# REV14.net
KiCad netlist of a schematic drawn in EAGLE
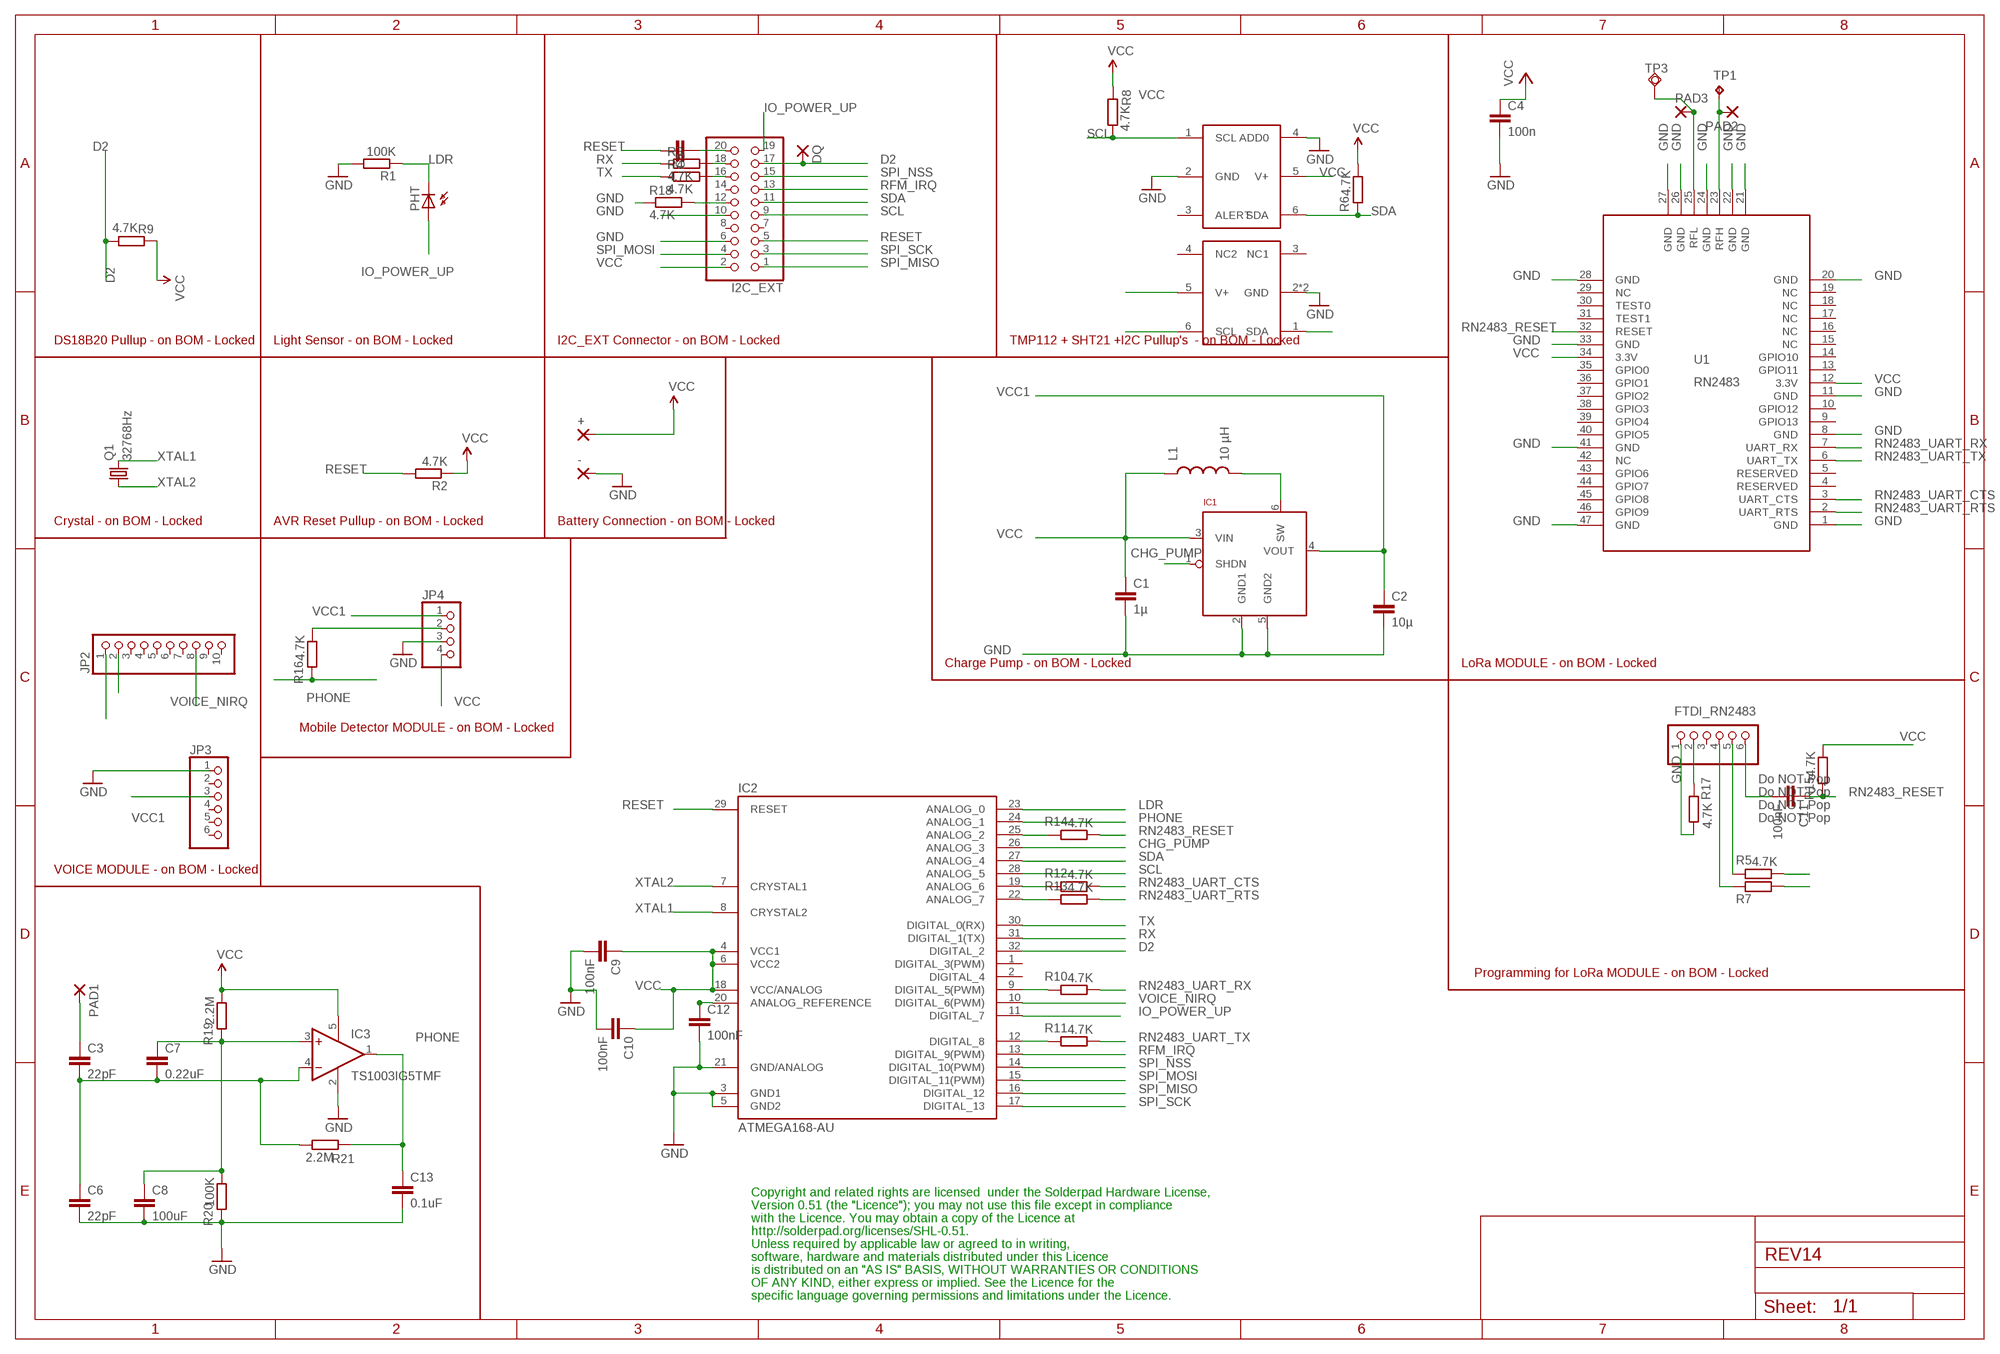
[diagram p0: schematic, sheet 1]

(export (version "E")
  (design (tool "Eeschema 10.0.6"))
  (components
    (comp (ref "+")
      (value "2,15/1,0")
      (footprint "eagle-import:2,15_1,0")
      (libsource (lib "eagle-import") (part "2,15/1,0"))
    )
    (comp (ref "-")
      (value "2,15/1,0")
      (footprint "eagle-import:2,15_1,0")
      (libsource (lib "eagle-import") (part "2,15/1,0"))
    )
    (comp (ref "C1")
      (value "1µ")
      (footprint "eagle-import:0603-CAP")
      (libsource (lib "eagle-import") (part "CAP0603-CAP"))
    )
    (comp (ref "C2")
      (value "10µ")
      (footprint "eagle-import:C0603")
      (libsource (lib "eagle-import") (part "C-EUC0603"))
    )
    (comp (ref "C3")
      (value "22pF")
      (footprint "eagle-import:C0603")
      (libsource (lib "eagle-import") (part "resistor_C-EUC0603"))
    )
    (comp (ref "C4")
      (value "100n")
      (footprint "eagle-import:C0603")
      (libsource (lib "eagle-import") (part "C-EUC0603"))
    )
    (comp (ref "C5")
      (value "100nF")
      (footprint "eagle-import:C0603")
      (libsource (lib "eagle-import") (part "resistor_C-EUC0603"))
    )
    (comp (ref "C6")
      (value "22pF")
      (footprint "eagle-import:C0603")
      (libsource (lib "eagle-import") (part "resistor_C-EUC0603"))
    )
    (comp (ref "C7")
      (value "0.22uF")
      (footprint "eagle-import:C050H075X075")
      (libsource (lib "eagle-import") (part "C-EU050H075X075"))
    )
    (comp (ref "C8")
      (value "100uF")
      (footprint "eagle-import:C1206")
      (libsource (lib "eagle-import") (part "C-EUC1206"))
    )
    (comp (ref "C9")
      (value "100nF")
      (footprint "eagle-import:C0603")
      (libsource (lib "eagle-import") (part "resistor_C-EUC0603"))
    )
    (comp (ref "C10")
      (value "100nF")
      (footprint "eagle-import:C0603")
      (libsource (lib "eagle-import") (part "resistor_C-EUC0603"))
    )
    (comp (ref "C11")
      (value "100nF")
      (footprint "eagle-import:C0603")
      (libsource (lib "eagle-import") (part "resistor_C-EUC0603"))
    )
    (comp (ref "C12")
      (value "100nF")
      (footprint "eagle-import:C0603")
      (libsource (lib "eagle-import") (part "resistor_C-EUC0603"))
    )
    (comp (ref "C13")
      (value "0.1uF")
      (footprint "eagle-import:C0603")
      (libsource (lib "eagle-import") (part "resistor_C-EUC0603"))
    )
    (comp (ref "DQ")
      (value "2,15/1,0")
      (footprint "eagle-import:2,15_1,0")
      (libsource (lib "eagle-import") (part "2,15/1,0"))
    )
    (comp (ref "FTDI_RN2483")
      (value "PINHD-1X6")
      (footprint "eagle-import:1X06")
      (libsource (lib "eagle-import") (part "PINHD-1X6"))
    )
    (comp (ref "I2C_EXT")
      (value "PINHD-2X10")
      (footprint "eagle-import:2X10")
      (libsource (lib "eagle-import") (part "PINHD-2X10"))
    )
    (comp (ref "IC1")
      (value "LTC3525")
      (footprint "eagle-import:SC70")
      (libsource (lib "eagle-import") (part "LTC3525"))
    )
    (comp (ref "IC2")
      (value "ATMEGA168-AU")
      (footprint "eagle-import:TQFP32-08")
      (libsource (lib "eagle-import") (part "ATMEGA168-AU"))
    )
    (comp (ref "IC3")
      (value "TS1003IG5TMF")
      (footprint "eagle-import:TS1003IG5T")
      (libsource (lib "eagle-import") (part "TS1003IG5TMF"))
    )
    (comp (ref "JP2")
      (value "PINHD-1X10")
      (footprint "eagle-import:1X10")
      (libsource (lib "eagle-import") (part "PINHD-1X10"))
    )
    (comp (ref "JP3")
      (value "PINHD-1X6")
      (footprint "eagle-import:1X06")
      (libsource (lib "eagle-import") (part "PINHD-1X6"))
    )
    (comp (ref "JP4")
      (value "PINHD-1X4")
      (footprint "eagle-import:1X04")
      (libsource (lib "eagle-import") (part "PINHD-1X4"))
    )
    (comp (ref "L1")
      (value "10 µH")
      (footprint "eagle-import:1210")
      (libsource (lib "eagle-import") (part "INDUCTOR1210"))
    )
    (comp (ref "PAD1")
      (value "2,15/1,0")
      (footprint "eagle-import:2,15_1,0")
      (libsource (lib "eagle-import") (part "2,15/1,0"))
    )
    (comp (ref "PAD2")
      (value "2,15/1,0")
      (footprint "eagle-import:2,15_1,0")
      (libsource (lib "eagle-import") (part "2,15/1,0"))
    )
    (comp (ref "PAD3")
      (value "2,15/1,0")
      (footprint "eagle-import:2,15_1,0")
      (libsource (lib "eagle-import") (part "2,15/1,0"))
    )
    (comp (ref "PHT")
      (value "BPX65")
      (footprint "eagle-import:BPX65")
      (fields (field (name "MPN") "BPX65."))
      (libsource (lib "eagle-import") (part "BPX65"))
    )
    (comp (ref "Q1")
      (value "32768Hz")
      (footprint "eagle-import:MC-306")
      (fields (field (name "MPN") "MC-306 60.0KHZ  100PPM ,12.5PF"))
      (libsource (lib "eagle-import") (part "MC-306"))
    )
    (comp (ref "R1")
      (value "100K")
      (footprint "eagle-import:R0603")
      (libsource (lib "eagle-import") (part "R-EU_R0603"))
    )
    (comp (ref "R2")
      (value "4.7K")
      (footprint "eagle-import:R0603")
      (libsource (lib "eagle-import") (part "R-EU_R0603"))
    )
    (comp (ref "R3")
      (value "4.7K")
      (footprint "eagle-import:R0603")
      (libsource (lib "eagle-import") (part "R-EU_R0603"))
    )
    (comp (ref "R4")
      (value "4.7K")
      (footprint "eagle-import:R0603")
      (libsource (lib "eagle-import") (part "R-EU_R0603"))
    )
    (comp (ref "R5")
      (value "4.7K")
      (footprint "eagle-import:R0603")
      (libsource (lib "eagle-import") (part "R-EU_R0603"))
    )
    (comp (ref "R6")
      (value "4.7K")
      (footprint "eagle-import:R0603")
      (libsource (lib "eagle-import") (part "R-EU_R0603"))
    )
    (comp (ref "R7")
      (value "4.7K")
      (footprint "eagle-import:R0603")
      (libsource (lib "eagle-import") (part "R-EU_R0603"))
    )
    (comp (ref "R8")
      (value "4.7K")
      (footprint "eagle-import:R0603")
      (libsource (lib "eagle-import") (part "R-EU_R0603"))
    )
    (comp (ref "R9")
      (value "4.7K")
      (footprint "eagle-import:R0603")
      (libsource (lib "eagle-import") (part "R-EU_R0603"))
    )
    (comp (ref "R10")
      (value "4.7K")
      (footprint "eagle-import:R0603")
      (libsource (lib "eagle-import") (part "R-EU_R0603"))
    )
    (comp (ref "R11")
      (value "4.7K")
      (footprint "eagle-import:R0603")
      (libsource (lib "eagle-import") (part "R-EU_R0603"))
    )
    (comp (ref "R12")
      (value "4.7K")
      (footprint "eagle-import:R0603")
      (libsource (lib "eagle-import") (part "R-EU_R0603"))
    )
    (comp (ref "R13")
      (value "4.7K")
      (footprint "eagle-import:R0603")
      (libsource (lib "eagle-import") (part "R-EU_R0603"))
    )
    (comp (ref "R14")
      (value "4.7K")
      (footprint "eagle-import:R0603")
      (libsource (lib "eagle-import") (part "R-EU_R0603"))
    )
    (comp (ref "R15")
      (value "4.7K")
      (footprint "eagle-import:R0603")
      (libsource (lib "eagle-import") (part "R-EU_R0603"))
    )
    (comp (ref "R16")
      (value "4.7K")
      (footprint "eagle-import:R0603")
      (libsource (lib "eagle-import") (part "R-EU_R0603"))
    )
    (comp (ref "R17")
      (value "4.7K")
      (footprint "eagle-import:R0603")
      (libsource (lib "eagle-import") (part "R-EU_R0603"))
    )
    (comp (ref "R18")
      (value "4.7K")
      (footprint "eagle-import:R0603")
      (libsource (lib "eagle-import") (part "R-EU_R0603"))
    )
    (comp (ref "R19")
      (value "2.2M")
      (footprint "eagle-import:R0603")
      (libsource (lib "eagle-import") (part "R-EU_R0603"))
    )
    (comp (ref "R20")
      (value "100K")
      (footprint "eagle-import:R0603")
      (libsource (lib "eagle-import") (part "R-EU_R0603"))
    )
    (comp (ref "R21")
      (value "2.2M")
      (footprint "eagle-import:R0603")
      (libsource (lib "eagle-import") (part "R-EU_R0603"))
    )
    (comp (ref "TP1")
      (value "TPB1,27")
      (footprint "eagle-import:B1,27")
      (libsource (lib "eagle-import") (part "TPB1,27"))
    )
    (comp (ref "TP3")
      (value "TPSQTP07R")
      (footprint "eagle-import:TP07R")
      (libsource (lib "eagle-import") (part "TPSQTP07R"))
    )
    (comp (ref "U$4")
      (value "SHT21")
      (footprint "eagle-import:SHT21")
      (libsource (lib "eagle-import") (part "SHT21"))
    )
    (comp (ref "U1")
      (value "RN2483")
      (footprint "eagle-import:RN2483")
      (libsource (lib "eagle-import") (part "RN2483"))
    )
    (comp (ref "U2")
      (value "TMP112")
      (footprint "eagle-import:TMP112")
      (libsource (lib "eagle-import") (part "TMP112"))
    )
  )
  (nets
    (net (code "1") (name "/CHG_PUMP") (class "Default")
      (node (ref "IC1") (pin "1") (pinfunction "SHDN_1") (pintype "input"))
      (node (ref "IC2") (pin "26") (pinfunction "ANALOG_3_26") (pintype "bidirectional"))
    )
    (net (code "2") (name "/D2") (class "Default")
      (node (ref "DQ") (pin "1") (pinfunction "P_1") (pintype "passive"))
      (node (ref "I2C_EXT") (pin "17") (pinfunction "17_17") (pintype "passive"))
      (node (ref "IC2") (pin "32") (pinfunction "DIGITAL_2_32") (pintype "bidirectional"))
      (node (ref "R9") (pin "1") (pinfunction "1_1") (pintype "passive"))
    )
    (net (code "3") (name "/IO_POWER_UP") (class "Default")
      (node (ref "I2C_EXT") (pin "19") (pinfunction "19_19") (pintype "passive"))
      (node (ref "IC2") (pin "11") (pinfunction "DIGITAL_7_11") (pintype "bidirectional"))
      (node (ref "PHT") (pin "A") (pinfunction "A_A") (pintype "passive"))
    )
    (net (code "4") (name "/LDR") (class "Default")
      (node (ref "IC2") (pin "23") (pinfunction "ANALOG_0_23") (pintype "bidirectional"))
      (node (ref "PHT") (pin "K") (pinfunction "C_K") (pintype "passive"))
      (node (ref "R1") (pin "1") (pinfunction "1_1") (pintype "passive"))
    )
    (net (code "5") (name "/PHONE") (class "Default")
      (node (ref "C13") (pin "1") (pinfunction "1_1") (pintype "passive"))
      (node (ref "IC2") (pin "24") (pinfunction "ANALOG_1_24") (pintype "bidirectional"))
      (node (ref "IC3") (pin "1") (pinfunction "OUT_1") (pintype "output"))
      (node (ref "R16") (pin "2") (pinfunction "2_2") (pintype "passive"))
      (node (ref "R21") (pin "2") (pinfunction "2_2") (pintype "passive"))
    )
    (net (code "6") (name "/RESET") (class "Default")
      (node (ref "C5") (pin "1") (pinfunction "1_1") (pintype "passive"))
      (node (ref "I2C_EXT") (pin "5") (pinfunction "5_5") (pintype "passive"))
      (node (ref "IC2") (pin "29") (pinfunction "RESET_29") (pintype "bidirectional"))
      (node (ref "R2") (pin "2") (pinfunction "2_2") (pintype "passive"))
    )
    (net (code "7") (name "/RFM_IRQ") (class "Default")
      (node (ref "I2C_EXT") (pin "13") (pinfunction "13_13") (pintype "passive"))
      (node (ref "IC2") (pin "13") (pinfunction "DIGITAL_9(PWM)_13") (pintype "bidirectional"))
    )
    (net (code "8") (name "/RN2483_RESET") (class "Default")
      (node (ref "C11") (pin "1") (pinfunction "1_1") (pintype "passive"))
      (node (ref "R14") (pin "1") (pinfunction "1_1") (pintype "passive"))
      (node (ref "R15") (pin "2") (pinfunction "2_2") (pintype "passive"))
      (node (ref "U1") (pin "32") (pinfunction "RESET_32") (pintype "input"))
    )
    (net (code "9") (name "/RN2483_UART_CTS") (class "Default")
      (node (ref "R12") (pin "1") (pinfunction "1_1") (pintype "passive"))
      (node (ref "U1") (pin "3") (pinfunction "UART_CTS_3") (pintype "bidirectional"))
    )
    (net (code "10") (name "/RN2483_UART_RTS") (class "Default")
      (node (ref "R13") (pin "1") (pinfunction "1_1") (pintype "passive"))
      (node (ref "U1") (pin "2") (pinfunction "UART_RTS_2") (pintype "bidirectional"))
    )
    (net (code "11") (name "/RN2483_UART_RX") (class "Default")
      (node (ref "R10") (pin "1") (pinfunction "1_1") (pintype "passive"))
      (node (ref "R7") (pin "1") (pinfunction "1_1") (pintype "passive"))
      (node (ref "U1") (pin "7") (pinfunction "UART_RX_7") (pintype "bidirectional"))
    )
    (net (code "12") (name "/RN2483_UART_TX") (class "Default")
      (node (ref "R11") (pin "1") (pinfunction "1_1") (pintype "passive"))
      (node (ref "R5") (pin "1") (pinfunction "1_1") (pintype "passive"))
      (node (ref "U1") (pin "6") (pinfunction "UART_TX_6") (pintype "bidirectional"))
    )
    (net (code "13") (name "/RX") (class "Default")
      (node (ref "IC2") (pin "31") (pinfunction "DIGITAL_1(TX)_31") (pintype "bidirectional"))
      (node (ref "R3") (pin "1") (pinfunction "1_1") (pintype "passive"))
    )
    (net (code "14") (name "/SCL") (class "Default")
      (node (ref "I2C_EXT") (pin "9") (pinfunction "9_9") (pintype "passive"))
      (node (ref "IC2") (pin "28") (pinfunction "ANALOG_5_28") (pintype "bidirectional"))
      (node (ref "JP2") (pin "1") (pinfunction "1_1") (pintype "passive"))
      (node (ref "R8") (pin "1") (pinfunction "1_1") (pintype "passive"))
      (node (ref "U$4") (pin "6") (pinfunction "SCL_6") (pintype "bidirectional"))
      (node (ref "U2") (pin "1") (pinfunction "SCL_1") (pintype "bidirectional"))
    )
    (net (code "15") (name "/SDA") (class "Default")
      (node (ref "I2C_EXT") (pin "11") (pinfunction "11_11") (pintype "passive"))
      (node (ref "IC2") (pin "27") (pinfunction "ANALOG_4_27") (pintype "bidirectional"))
      (node (ref "JP2") (pin "2") (pinfunction "2_2") (pintype "passive"))
      (node (ref "R6") (pin "2") (pinfunction "2_2") (pintype "passive"))
      (node (ref "U$4") (pin "1") (pinfunction "SDA_1") (pintype "bidirectional"))
      (node (ref "U2") (pin "6") (pinfunction "SDA_6") (pintype "bidirectional"))
    )
    (net (code "16") (name "/SPI_MISO") (class "Default")
      (node (ref "I2C_EXT") (pin "1") (pinfunction "1_1") (pintype "passive"))
      (node (ref "IC2") (pin "16") (pinfunction "DIGITAL_12_16") (pintype "bidirectional"))
    )
    (net (code "17") (name "/SPI_MOSI") (class "Default")
      (node (ref "I2C_EXT") (pin "4") (pinfunction "4_4") (pintype "passive"))
      (node (ref "IC2") (pin "15") (pinfunction "DIGITAL_11(PWM)_15") (pintype "bidirectional"))
    )
    (net (code "18") (name "/SPI_NSS") (class "Default")
      (node (ref "I2C_EXT") (pin "15") (pinfunction "15_15") (pintype "passive"))
      (node (ref "IC2") (pin "14") (pinfunction "DIGITAL_10(PWM)_14") (pintype "bidirectional"))
    )
    (net (code "19") (name "/SPI_SCK") (class "Default")
      (node (ref "I2C_EXT") (pin "3") (pinfunction "3_3") (pintype "passive"))
      (node (ref "IC2") (pin "17") (pinfunction "DIGITAL_13_17") (pintype "bidirectional"))
    )
    (net (code "20") (name "/TX") (class "Default")
      (node (ref "IC2") (pin "30") (pinfunction "DIGITAL_0(RX)_30") (pintype "bidirectional"))
      (node (ref "R4") (pin "1") (pinfunction "1_1") (pintype "passive"))
    )
    (net (code "21") (name "/VCC1") (class "Default")
      (node (ref "C2") (pin "1") (pinfunction "1_1") (pintype "passive"))
      (node (ref "IC1") (pin "4") (pinfunction "VOUT_4") (pintype "power_in"))
      (node (ref "JP3") (pin "3") (pinfunction "3_3") (pintype "passive"))
      (node (ref "JP4") (pin "1") (pinfunction "1_1") (pintype "passive"))
    )
    (net (code "22") (name "/VOICE_NIRQ") (class "Default")
      (node (ref "IC2") (pin "10") (pinfunction "DIGITAL_6(PWM)_10") (pintype "bidirectional"))
      (node (ref "JP2") (pin "8") (pinfunction "8_8") (pintype "passive"))
    )
    (net (code "23") (name "/XTAL1") (class "Default")
      (node (ref "IC2") (pin "8") (pinfunction "CRYSTAL2_8") (pintype "bidirectional"))
      (node (ref "Q1") (pin "4") (pinfunction "2_4") (pintype "passive"))
    )
    (net (code "24") (name "/XTAL2") (class "Default")
      (node (ref "IC2") (pin "7") (pinfunction "CRYSTAL1_7") (pintype "bidirectional"))
      (node (ref "Q1") (pin "1") (pinfunction "1_1") (pintype "passive"))
    )
    (net (code "25") (name "GND") (class "Default")
      (node (ref "-") (pin "1") (pinfunction "P_1") (pintype "passive"))
      (node (ref "C1") (pin "2") (pinfunction "2_2") (pintype "passive"))
      (node (ref "C10") (pin "2") (pinfunction "2_2") (pintype "passive"))
      (node (ref "C12") (pin "2") (pinfunction "2_2") (pintype "passive"))
      (node (ref "C13") (pin "2") (pinfunction "2_2") (pintype "passive"))
      (node (ref "C2") (pin "2") (pinfunction "2_2") (pintype "passive"))
      (node (ref "C4") (pin "2") (pinfunction "2_2") (pintype "passive"))
      (node (ref "C6") (pin "2") (pinfunction "2_2") (pintype "passive"))
      (node (ref "C8") (pin "2") (pinfunction "2_2") (pintype "passive"))
      (node (ref "C9") (pin "2") (pinfunction "2_2") (pintype "passive"))
      (node (ref "FTDI_RN2483") (pin "1") (pinfunction "1_1") (pintype "passive"))
      (node (ref "I2C_EXT") (pin "10") (pinfunction "10_10") (pintype "passive"))
      (node (ref "I2C_EXT") (pin "6") (pinfunction "6_6") (pintype "passive"))
      (node (ref "IC1") (pin "2") (pinfunction "GND1_2") (pintype "power_in"))
      (node (ref "IC1") (pin "5") (pinfunction "GND2_5") (pintype "power_in"))
      (node (ref "IC2") (pin "21") (pinfunction "GND/ANALOG_21") (pintype "power_in"))
      (node (ref "IC2") (pin "3") (pinfunction "GND1_3") (pintype "power_in"))
      (node (ref "IC2") (pin "5") (pinfunction "GND2_5") (pintype "power_in"))
      (node (ref "IC3") (pin "2") (pinfunction "V-_2") (pintype "power_in"))
      (node (ref "JP3") (pin "1") (pinfunction "1_1") (pintype "passive"))
      (node (ref "JP4") (pin "3") (pinfunction "3_3") (pintype "passive"))
      (node (ref "R1") (pin "2") (pinfunction "2_2") (pintype "passive"))
      (node (ref "R17") (pin "2") (pinfunction "2_2") (pintype "passive"))
      (node (ref "R18") (pin "1") (pinfunction "1_1") (pintype "passive"))
      (node (ref "R20") (pin "2") (pinfunction "2_2") (pintype "passive"))
      (node (ref "U$4") (pin "2") (pinfunction "GND_2") (pintype "bidirectional"))
      (node (ref "U$4") (pin "P$1") (pinfunction "GND_P$1") (pintype "bidirectional"))
      (node (ref "U1") (pin "1") (pinfunction "GND_1") (pintype "power_in"))
      (node (ref "U1") (pin "11") (pinfunction "GND_11") (pintype "power_in"))
      (node (ref "U1") (pin "20") (pinfunction "GND_20") (pintype "input"))
      (node (ref "U1") (pin "21") (pinfunction "GND_21") (pintype "input"))
      (node (ref "U1") (pin "22") (pinfunction "GND_22") (pintype "input"))
      (node (ref "U1") (pin "24") (pinfunction "GND_24") (pintype "bidirectional"))
      (node (ref "U1") (pin "26") (pinfunction "GND_26") (pintype "bidirectional"))
      (node (ref "U1") (pin "27") (pinfunction "GND_27") (pintype "bidirectional"))
      (node (ref "U1") (pin "28") (pinfunction "GND_28") (pintype "bidirectional"))
      (node (ref "U1") (pin "33") (pinfunction "GND_33") (pintype "bidirectional"))
      (node (ref "U1") (pin "41") (pinfunction "GND_41") (pintype "bidirectional"))
      (node (ref "U1") (pin "47") (pinfunction "GND_47") (pintype "bidirectional"))
      (node (ref "U1") (pin "8") (pinfunction "GND_8") (pintype "power_in"))
      (node (ref "U2") (pin "2") (pinfunction "GND_2") (pintype "bidirectional"))
      (node (ref "U2") (pin "4") (pinfunction "ADD0_4") (pintype "bidirectional"))
    )
    (net (code "26") (name "Net-(C5-Pad2)") (class "Default")
      (node (ref "C5") (pin "2") (pinfunction "2_2") (pintype "passive"))
      (node (ref "I2C_EXT") (pin "20") (pinfunction "20_20") (pintype "passive"))
    )
    (net (code "27") (name "Net-(C11-Pad2)") (class "Default")
      (node (ref "C11") (pin "2") (pinfunction "2_2") (pintype "passive"))
      (node (ref "FTDI_RN2483") (pin "6") (pinfunction "6_6") (pintype "passive"))
    )
    (net (code "28") (name "Net-(FTDI_RN2483-Pad2)") (class "Default")
      (node (ref "FTDI_RN2483") (pin "2") (pinfunction "2_2") (pintype "passive"))
      (node (ref "R17") (pin "1") (pinfunction "1_1") (pintype "passive"))
    )
    (net (code "29") (name "Net-(FTDI_RN2483-Pad4)") (class "Default")
      (node (ref "FTDI_RN2483") (pin "4") (pinfunction "4_4") (pintype "passive"))
      (node (ref "R7") (pin "2") (pinfunction "2_2") (pintype "passive"))
    )
    (net (code "30") (name "Net-(FTDI_RN2483-Pad5)") (class "Default")
      (node (ref "FTDI_RN2483") (pin "5") (pinfunction "5_5") (pintype "passive"))
      (node (ref "R5") (pin "2") (pinfunction "2_2") (pintype "passive"))
    )
    (net (code "31") (name "Net-(I2C_EXT-Pad12)") (class "Default")
      (node (ref "I2C_EXT") (pin "12") (pinfunction "12_12") (pintype "passive"))
      (node (ref "R18") (pin "2") (pinfunction "2_2") (pintype "passive"))
    )
    (net (code "32") (name "Net-(I2C_EXT-Pad16)") (class "Default")
      (node (ref "I2C_EXT") (pin "16") (pinfunction "16_16") (pintype "passive"))
      (node (ref "R4") (pin "2") (pinfunction "2_2") (pintype "passive"))
    )
    (net (code "33") (name "Net-(I2C_EXT-Pad18)") (class "Default")
      (node (ref "I2C_EXT") (pin "18") (pinfunction "18_18") (pintype "passive"))
      (node (ref "R3") (pin "2") (pinfunction "2_2") (pintype "passive"))
    )
    (net (code "34") (name "Net-(IC1-SW)") (class "Default")
      (node (ref "IC1") (pin "6") (pinfunction "SW_6") (pintype "power_in"))
      (node (ref "L1") (pin "2") (pinfunction "2_2") (pintype "passive"))
    )
    (net (code "35") (name "Net-(IC2-ANALOG_2)") (class "Default")
      (node (ref "IC2") (pin "25") (pinfunction "ANALOG_2_25") (pintype "bidirectional"))
      (node (ref "R14") (pin "2") (pinfunction "2_2") (pintype "passive"))
    )
    (net (code "36") (name "Net-(IC2-ANALOG_6)") (class "Default")
      (node (ref "IC2") (pin "19") (pinfunction "ANALOG_6_19") (pintype "passive"))
      (node (ref "R12") (pin "2") (pinfunction "2_2") (pintype "passive"))
    )
    (net (code "37") (name "Net-(IC2-ANALOG_7)") (class "Default")
      (node (ref "IC2") (pin "22") (pinfunction "ANALOG_7_22") (pintype "passive"))
      (node (ref "R13") (pin "2") (pinfunction "2_2") (pintype "passive"))
    )
    (net (code "38") (name "Net-(IC2-ANALOG_REFERENCE)") (class "Default")
      (node (ref "C12") (pin "1") (pinfunction "1_1") (pintype "passive"))
      (node (ref "IC2") (pin "20") (pinfunction "ANALOG_REFERENCE_20") (pintype "passive"))
    )
    (net (code "39") (name "Net-(IC2-DIGITAL_5(PWM))") (class "Default")
      (node (ref "IC2") (pin "9") (pinfunction "DIGITAL_5(PWM)_9") (pintype "bidirectional"))
      (node (ref "R10") (pin "2") (pinfunction "2_2") (pintype "passive"))
    )
    (net (code "40") (name "Net-(IC2-DIGITAL_8)") (class "Default")
      (node (ref "IC2") (pin "12") (pinfunction "DIGITAL_8_12") (pintype "bidirectional"))
      (node (ref "R11") (pin "2") (pinfunction "2_2") (pintype "passive"))
    )
    (net (code "41") (name "Net-(IC3-+IN)") (class "Default")
      (node (ref "C7") (pin "1") (pinfunction "1_1") (pintype "passive"))
      (node (ref "C8") (pin "1") (pinfunction "1_1") (pintype "passive"))
      (node (ref "IC3") (pin "3") (pinfunction "+IN_3") (pintype "input"))
      (node (ref "R19") (pin "2") (pinfunction "2_2") (pintype "passive"))
      (node (ref "R20") (pin "1") (pinfunction "1_1") (pintype "passive"))
    )
    (net (code "42") (name "Net-(IC3--IN)") (class "Default")
      (node (ref "C3") (pin "2") (pinfunction "2_2") (pintype "passive"))
      (node (ref "C6") (pin "1") (pinfunction "1_1") (pintype "passive"))
      (node (ref "C7") (pin "2") (pinfunction "2_2") (pintype "passive"))
      (node (ref "IC3") (pin "4") (pinfunction "-IN_4") (pintype "input"))
      (node (ref "R21") (pin "1") (pinfunction "1_1") (pintype "passive"))
    )
    (net (code "43") (name "Net-(JP4-Pad2)") (class "Default")
      (node (ref "JP4") (pin "2") (pinfunction "2_2") (pintype "passive"))
      (node (ref "R16") (pin "1") (pinfunction "1_1") (pintype "passive"))
    )
    (net (code "44") (name "Net-(PAD1-P)") (class "Default")
      (node (ref "C3") (pin "1") (pinfunction "1_1") (pintype "passive"))
      (node (ref "PAD1") (pin "1") (pinfunction "P_1") (pintype "passive"))
    )
    (net (code "45") (name "Net-(PAD2-P)") (class "Default")
      (node (ref "PAD2") (pin "1") (pinfunction "P_1") (pintype "passive"))
      (node (ref "TP1") (pin "TP") (pinfunction "TP_TP") (pintype "input"))
      (node (ref "U1") (pin "23") (pinfunction "RFH_23") (pintype "bidirectional"))
    )
    (net (code "46") (name "Net-(PAD3-P)") (class "Default")
      (node (ref "PAD3") (pin "1") (pinfunction "P_1") (pintype "passive"))
      (node (ref "TP3") (pin "TP") (pinfunction "TP_TP") (pintype "input"))
      (node (ref "U1") (pin "25") (pinfunction "RFL_25") (pintype "bidirectional"))
    )
    (net (code "47") (name "VCC") (class "Default")
      (node (ref "+") (pin "1") (pinfunction "P_1") (pintype "passive"))
      (node (ref "C1") (pin "1") (pinfunction "1_1") (pintype "passive"))
      (node (ref "C10") (pin "1") (pinfunction "1_1") (pintype "passive"))
      (node (ref "C4") (pin "1") (pinfunction "1_1") (pintype "passive"))
      (node (ref "C9") (pin "1") (pinfunction "1_1") (pintype "passive"))
      (node (ref "I2C_EXT") (pin "2") (pinfunction "2_2") (pintype "passive"))
      (node (ref "IC1") (pin "3") (pinfunction "VIN_3") (pintype "tri_state"))
      (node (ref "IC2") (pin "18") (pinfunction "VCC/ANALOG_18") (pintype "passive"))
      (node (ref "IC2") (pin "4") (pinfunction "VCC1_4") (pintype "power_in"))
      (node (ref "IC2") (pin "6") (pinfunction "VCC2_6") (pintype "power_in"))
      (node (ref "IC3") (pin "5") (pinfunction "V+_5") (pintype "power_in"))
      (node (ref "JP4") (pin "4") (pinfunction "4_4") (pintype "passive"))
      (node (ref "L1") (pin "1") (pinfunction "1_1") (pintype "passive"))
      (node (ref "R15") (pin "1") (pinfunction "1_1") (pintype "passive"))
      (node (ref "R19") (pin "1") (pinfunction "1_1") (pintype "passive"))
      (node (ref "R2") (pin "1") (pinfunction "1_1") (pintype "passive"))
      (node (ref "R6") (pin "1") (pinfunction "1_1") (pintype "passive"))
      (node (ref "R8") (pin "2") (pinfunction "2_2") (pintype "passive"))
      (node (ref "R9") (pin "2") (pinfunction "2_2") (pintype "passive"))
      (node (ref "U$4") (pin "5") (pinfunction "V+_5") (pintype "bidirectional"))
      (node (ref "U1") (pin "12") (pinfunction "3.3V_12") (pintype "power_in"))
      (node (ref "U1") (pin "34") (pinfunction "3.3V_34") (pintype "power_in"))
      (node (ref "U2") (pin "5") (pinfunction "V+_5") (pintype "bidirectional"))
    )
    (net (code "48") (name "unconnected-(FTDI_RN2483-Pad3)") (class "Default")
      (node (ref "FTDI_RN2483") (pin "3") (pinfunction "3_3") (pintype "passive"))
    )
    (net (code "49") (name "unconnected-(I2C_EXT-Pad7)") (class "Default")
      (node (ref "I2C_EXT") (pin "7") (pinfunction "7_7") (pintype "passive"))
    )
    (net (code "50") (name "unconnected-(I2C_EXT-Pad8)") (class "Default")
      (node (ref "I2C_EXT") (pin "8") (pinfunction "8_8") (pintype "passive"))
    )
    (net (code "51") (name "unconnected-(I2C_EXT-Pad14)") (class "Default")
      (node (ref "I2C_EXT") (pin "14") (pinfunction "14_14") (pintype "passive"))
    )
    (net (code "52") (name "unconnected-(IC2-DIGITAL_3(PWM)-Pad1)") (class "Default")
      (node (ref "IC2") (pin "1") (pinfunction "DIGITAL_3(PWM)_1") (pintype "bidirectional"))
    )
    (net (code "53") (name "unconnected-(IC2-DIGITAL_4-Pad2)") (class "Default")
      (node (ref "IC2") (pin "2") (pinfunction "DIGITAL_4_2") (pintype "bidirectional"))
    )
    (net (code "54") (name "unconnected-(JP2-Pad3)") (class "Default")
      (node (ref "JP2") (pin "3") (pinfunction "3_3") (pintype "passive"))
    )
    (net (code "55") (name "unconnected-(JP2-Pad4)") (class "Default")
      (node (ref "JP2") (pin "4") (pinfunction "4_4") (pintype "passive"))
    )
    (net (code "56") (name "unconnected-(JP2-Pad5)") (class "Default")
      (node (ref "JP2") (pin "5") (pinfunction "5_5") (pintype "passive"))
    )
    (net (code "57") (name "unconnected-(JP2-Pad6)") (class "Default")
      (node (ref "JP2") (pin "6") (pinfunction "6_6") (pintype "passive"))
    )
    (net (code "58") (name "unconnected-(JP2-Pad7)") (class "Default")
      (node (ref "JP2") (pin "7") (pinfunction "7_7") (pintype "passive"))
    )
    (net (code "59") (name "unconnected-(JP2-Pad9)") (class "Default")
      (node (ref "JP2") (pin "9") (pinfunction "9_9") (pintype "passive"))
    )
    (net (code "60") (name "unconnected-(JP2-Pad10)") (class "Default")
      (node (ref "JP2") (pin "10") (pinfunction "10_10") (pintype "passive"))
    )
    (net (code "61") (name "unconnected-(JP3-Pad2)") (class "Default")
      (node (ref "JP3") (pin "2") (pinfunction "2_2") (pintype "passive"))
    )
    (net (code "62") (name "unconnected-(JP3-Pad4)") (class "Default")
      (node (ref "JP3") (pin "4") (pinfunction "4_4") (pintype "passive"))
    )
    (net (code "63") (name "unconnected-(JP3-Pad5)") (class "Default")
      (node (ref "JP3") (pin "5") (pinfunction "5_5") (pintype "passive"))
    )
    (net (code "64") (name "unconnected-(JP3-Pad6)") (class "Default")
      (node (ref "JP3") (pin "6") (pinfunction "6_6") (pintype "passive"))
    )
    (net (code "65") (name "unconnected-(U$4-NC1-Pad3)") (class "Default")
      (node (ref "U$4") (pin "3") (pinfunction "NC1_3") (pintype "bidirectional"))
    )
    (net (code "66") (name "unconnected-(U$4-NC2-Pad4)") (class "Default")
      (node (ref "U$4") (pin "4") (pinfunction "NC2_4") (pintype "bidirectional"))
    )
    (net (code "67") (name "unconnected-(U1-GPIO0-Pad35)") (class "Default")
      (node (ref "U1") (pin "35") (pinfunction "GPIO0_35") (pintype "bidirectional"))
    )
    (net (code "68") (name "unconnected-(U1-GPIO1-Pad36)") (class "Default")
      (node (ref "U1") (pin "36") (pinfunction "GPIO1_36") (pintype "bidirectional"))
    )
    (net (code "69") (name "unconnected-(U1-GPIO2-Pad37)") (class "Default")
      (node (ref "U1") (pin "37") (pinfunction "GPIO2_37") (pintype "bidirectional"))
    )
    (net (code "70") (name "unconnected-(U1-GPIO3-Pad38)") (class "Default")
      (node (ref "U1") (pin "38") (pinfunction "GPIO3_38") (pintype "bidirectional"))
    )
    (net (code "71") (name "unconnected-(U1-GPIO4-Pad39)") (class "Default")
      (node (ref "U1") (pin "39") (pinfunction "GPIO4_39") (pintype "bidirectional"))
    )
    (net (code "72") (name "unconnected-(U1-GPIO5-Pad40)") (class "Default")
      (node (ref "U1") (pin "40") (pinfunction "GPIO5_40") (pintype "bidirectional"))
    )
    (net (code "73") (name "unconnected-(U1-GPIO6-Pad43)") (class "Default")
      (node (ref "U1") (pin "43") (pinfunction "GPIO6_43") (pintype "bidirectional"))
    )
    (net (code "74") (name "unconnected-(U1-GPIO7-Pad44)") (class "Default")
      (node (ref "U1") (pin "44") (pinfunction "GPIO7_44") (pintype "bidirectional"))
    )
    (net (code "75") (name "unconnected-(U1-GPIO8-Pad45)") (class "Default")
      (node (ref "U1") (pin "45") (pinfunction "GPIO8_45") (pintype "bidirectional"))
    )
    (net (code "76") (name "unconnected-(U1-GPIO9-Pad46)") (class "Default")
      (node (ref "U1") (pin "46") (pinfunction "GPIO9_46") (pintype "bidirectional"))
    )
    (net (code "77") (name "unconnected-(U1-GPIO10-Pad14)") (class "Default")
      (node (ref "U1") (pin "14") (pinfunction "GPIO10_14") (pintype "bidirectional"))
    )
    (net (code "78") (name "unconnected-(U1-GPIO11-Pad13)") (class "Default")
      (node (ref "U1") (pin "13") (pinfunction "GPIO11_13") (pintype "bidirectional"))
    )
    (net (code "79") (name "unconnected-(U1-GPIO12-Pad10)") (class "Default")
      (node (ref "U1") (pin "10") (pinfunction "GPIO12_10") (pintype "bidirectional"))
    )
    (net (code "80") (name "unconnected-(U1-GPIO13-Pad9)") (class "Default")
      (node (ref "U1") (pin "9") (pinfunction "GPIO13_9") (pintype "bidirectional"))
    )
    (net (code "81") (name "unconnected-(U1-NC-Pad15)") (class "Default")
      (node (ref "U1") (pin "15") (pinfunction "NC_15") (pintype "bidirectional"))
    )
    (net (code "82") (name "unconnected-(U1-NC-Pad16)") (class "Default")
      (node (ref "U1") (pin "16") (pinfunction "NC_16") (pintype "bidirectional"))
    )
    (net (code "83") (name "unconnected-(U1-NC-Pad17)") (class "Default")
      (node (ref "U1") (pin "17") (pinfunction "NC_17") (pintype "bidirectional"))
    )
    (net (code "84") (name "unconnected-(U1-NC-Pad18)") (class "Default")
      (node (ref "U1") (pin "18") (pinfunction "NC_18") (pintype "bidirectional"))
    )
    (net (code "85") (name "unconnected-(U1-NC-Pad19)") (class "Default")
      (node (ref "U1") (pin "19") (pinfunction "NC_19") (pintype "bidirectional"))
    )
    (net (code "86") (name "unconnected-(U1-NC-Pad29)") (class "Default")
      (node (ref "U1") (pin "29") (pinfunction "NC_29") (pintype "bidirectional"))
    )
    (net (code "87") (name "unconnected-(U1-NC-Pad42)") (class "Default")
      (node (ref "U1") (pin "42") (pinfunction "NC_42") (pintype "bidirectional"))
    )
    (net (code "88") (name "unconnected-(U1-RESERVED-Pad4)") (class "Default")
      (node (ref "U1") (pin "4") (pinfunction "RESERVED_4") (pintype "bidirectional"))
    )
    (net (code "89") (name "unconnected-(U1-RESERVED-Pad5)") (class "Default")
      (node (ref "U1") (pin "5") (pinfunction "RESERVED_5") (pintype "bidirectional"))
    )
    (net (code "90") (name "unconnected-(U1-TEST0-Pad30)") (class "Default")
      (node (ref "U1") (pin "30") (pinfunction "TEST0_30") (pintype "bidirectional"))
    )
    (net (code "91") (name "unconnected-(U1-TEST1-Pad31)") (class "Default")
      (node (ref "U1") (pin "31") (pinfunction "TEST1_31") (pintype "bidirectional"))
    )
    (net (code "92") (name "unconnected-(U2-ALERT-Pad3)") (class "Default")
      (node (ref "U2") (pin "3") (pinfunction "ALERT_3") (pintype "bidirectional"))
    )
  )
)
